# Lilypad_buffered.net
KiCad netlist of a schematic drawn in EAGLE
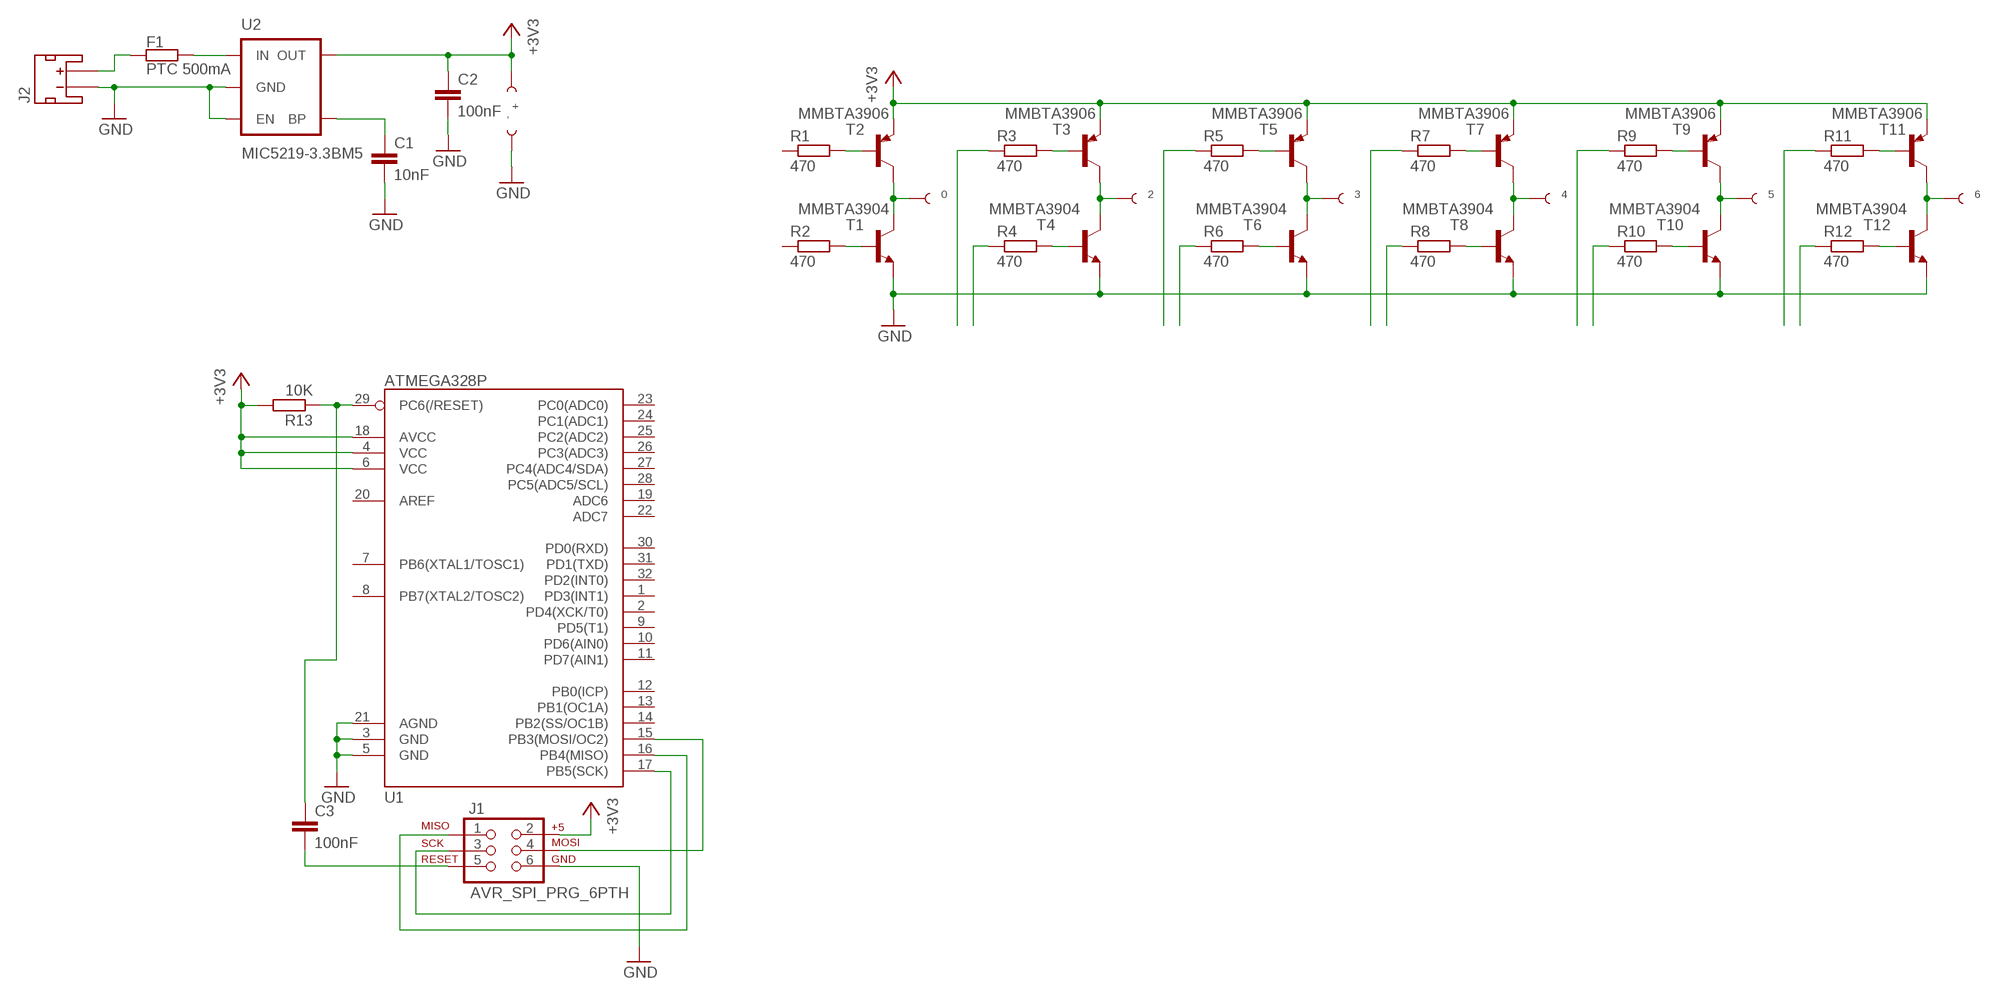
[diagram p0: schematic, sheet 1]

(export (version "E")
  (design (tool "Eeschema 10.0.6"))
  (components
    (comp (ref "C1")
      (value "10nF")
      (footprint "eagle-import:C0805K")
      (libsource (lib "eagle-import") (part "C-EUC0805K"))
    )
    (comp (ref "C2")
      (value "100nF")
      (footprint "eagle-import:C0805K")
      (libsource (lib "eagle-import") (part "C-EUC0805K"))
    )
    (comp (ref "C3")
      (value "100nF")
      (footprint "eagle-import:C0805K")
      (libsource (lib "eagle-import") (part "C-EUC0805K"))
    )
    (comp (ref "F1")
      (value "PTC 500mA")
      (footprint "eagle-import:SMD-2012")
      (libsource (lib "eagle-import") (part "RESISTENCIA-SMD-2012"))
    )
    (comp (ref "J1")
      (value "AVR_SPI_PRG_6PTH")
      (footprint "eagle-import:2X3")
      (libsource (lib "eagle-import") (part "AVR_SPI_PRG_6PTH"))
    )
    (comp (ref "J2")
      (value "JST_2MM_MALE")
      (footprint "eagle-import:JST-2-SMD")
      (libsource (lib "eagle-import") (part "JST_2MM_MALE"))
    )
    (comp (ref "R1")
      (value "470")
      (footprint "eagle-import:R0603")
      (libsource (lib "eagle-import") (part "R-EU_R0603"))
    )
    (comp (ref "R2")
      (value "470")
      (footprint "eagle-import:R0603")
      (libsource (lib "eagle-import") (part "R-EU_R0603"))
    )
    (comp (ref "R3")
      (value "470")
      (footprint "eagle-import:R0603")
      (libsource (lib "eagle-import") (part "R-EU_R0603"))
    )
    (comp (ref "R4")
      (value "470")
      (footprint "eagle-import:R0603")
      (libsource (lib "eagle-import") (part "R-EU_R0603"))
    )
    (comp (ref "R5")
      (value "470")
      (footprint "eagle-import:R0603")
      (libsource (lib "eagle-import") (part "R-EU_R0603"))
    )
    (comp (ref "R6")
      (value "470")
      (footprint "eagle-import:R0603")
      (libsource (lib "eagle-import") (part "R-EU_R0603"))
    )
    (comp (ref "R7")
      (value "470")
      (footprint "eagle-import:R0603")
      (libsource (lib "eagle-import") (part "R-EU_R0603"))
    )
    (comp (ref "R8")
      (value "470")
      (footprint "eagle-import:R0603")
      (libsource (lib "eagle-import") (part "R-EU_R0603"))
    )
    (comp (ref "R9")
      (value "470")
      (footprint "eagle-import:R0603")
      (libsource (lib "eagle-import") (part "R-EU_R0603"))
    )
    (comp (ref "R10")
      (value "470")
      (footprint "eagle-import:R0603")
      (libsource (lib "eagle-import") (part "R-EU_R0603"))
    )
    (comp (ref "R11")
      (value "470")
      (footprint "eagle-import:R0603")
      (libsource (lib "eagle-import") (part "R-EU_R0603"))
    )
    (comp (ref "R12")
      (value "470")
      (footprint "eagle-import:R0603")
      (libsource (lib "eagle-import") (part "R-EU_R0603"))
    )
    (comp (ref "R13")
      (value "10K")
      (footprint "eagle-import:R0603")
      (libsource (lib "eagle-import") (part "R-EU_R0603"))
    )
    (comp (ref "T1")
      (value "MMBTA3904")
      (footprint "eagle-import:SOT23-BEC")
      (libsource (lib "eagle-import") (part "-NPN-SOT23-BECMMBT3904LT1"))
    )
    (comp (ref "T2")
      (value "MMBTA3906")
      (footprint "eagle-import:SOT23-BEC")
      (libsource (lib "eagle-import") (part "-PNP-SOT23-BECMMBT3906LT1"))
    )
    (comp (ref "T3")
      (value "MMBTA3906")
      (footprint "eagle-import:SOT23-BEC")
      (libsource (lib "eagle-import") (part "-PNP-SOT23-BECMMBT3906LT1"))
    )
    (comp (ref "T4")
      (value "MMBTA3904")
      (footprint "eagle-import:SOT23-BEC")
      (libsource (lib "eagle-import") (part "-NPN-SOT23-BECMMBT3904LT1"))
    )
    (comp (ref "T5")
      (value "MMBTA3906")
      (footprint "eagle-import:SOT23-BEC")
      (libsource (lib "eagle-import") (part "-PNP-SOT23-BECMMBT3906LT1"))
    )
    (comp (ref "T6")
      (value "MMBTA3904")
      (footprint "eagle-import:SOT23-BEC")
      (libsource (lib "eagle-import") (part "-NPN-SOT23-BECMMBT3904LT1"))
    )
    (comp (ref "T7")
      (value "MMBTA3906")
      (footprint "eagle-import:SOT23-BEC")
      (libsource (lib "eagle-import") (part "-PNP-SOT23-BECMMBT3906LT1"))
    )
    (comp (ref "T8")
      (value "MMBTA3904")
      (footprint "eagle-import:SOT23-BEC")
      (libsource (lib "eagle-import") (part "-NPN-SOT23-BECMMBT3904LT1"))
    )
    (comp (ref "T9")
      (value "MMBTA3906")
      (footprint "eagle-import:SOT23-BEC")
      (libsource (lib "eagle-import") (part "-PNP-SOT23-BECMMBT3906LT1"))
    )
    (comp (ref "T10")
      (value "MMBTA3904")
      (footprint "eagle-import:SOT23-BEC")
      (libsource (lib "eagle-import") (part "-NPN-SOT23-BECMMBT3904LT1"))
    )
    (comp (ref "T11")
      (value "MMBTA3906")
      (footprint "eagle-import:SOT23-BEC")
      (libsource (lib "eagle-import") (part "-PNP-SOT23-BECMMBT3906LT1"))
    )
    (comp (ref "T12")
      (value "MMBTA3904")
      (footprint "eagle-import:SOT23-BEC")
      (libsource (lib "eagle-import") (part "-NPN-SOT23-BECMMBT3904LT1"))
    )
    (comp (ref "U$1")
      (value "0")
      (footprint "eagle-import:PETAL-LONG-1-2SIDE")
      (libsource (lib "eagle-import") (part "SEWTAP9"))
    )
    (comp (ref "U$2")
      (value "2")
      (footprint "eagle-import:PETAL-LONG-1-2SIDE")
      (libsource (lib "eagle-import") (part "SEWTAP9"))
    )
    (comp (ref "U$3")
      (value "3")
      (footprint "eagle-import:PETAL-LONG-1-2SIDE")
      (libsource (lib "eagle-import") (part "SEWTAP9"))
    )
    (comp (ref "U$4")
      (value "4")
      (footprint "eagle-import:PETAL-LONG-1-2SIDE")
      (libsource (lib "eagle-import") (part "SEWTAP9"))
    )
    (comp (ref "U$5")
      (value "5")
      (footprint "eagle-import:PETAL-LONG-1-2SIDE")
      (libsource (lib "eagle-import") (part "SEWTAP9"))
    )
    (comp (ref "U$6")
      (value "6")
      (footprint "eagle-import:PETAL-LONG-1-2SIDE")
      (libsource (lib "eagle-import") (part "SEWTAP9"))
    )
    (comp (ref "U$9")
      (value "+")
      (footprint "eagle-import:PETAL-LONG-1-2SIDE")
      (libsource (lib "eagle-import") (part "SEWTAP9"))
    )
    (comp (ref "U$10")
      (value "-")
      (footprint "eagle-import:PETAL-LONG-1-2SIDE")
      (libsource (lib "eagle-import") (part "SEWTAP9"))
    )
    (comp (ref "U1")
      (value "ATMEGA328P")
      (footprint "eagle-import:TQFP32-08")
      (libsource (lib "eagle-import") (part "ATMEGA328_SMT"))
    )
    (comp (ref "U2")
      (value "MIC5219-3.3BM5")
      (footprint "eagle-import:SOT23-5")
      (libsource (lib "eagle-import") (part "MIC52053.3V"))
    )
  )
  (nets
    (net (code "1") (name "+3V3") (class "Default")
      (node (ref "C2") (pin "1") (pinfunction "1_1") (pintype "passive"))
      (node (ref "J1") (pin "2") (pinfunction "2_2") (pintype "passive"))
      (node (ref "R13") (pin "2") (pinfunction "2_2") (pintype "passive"))
      (node (ref "T11") (pin "E") (pinfunction "E_E") (pintype "passive"))
      (node (ref "T2") (pin "E") (pinfunction "E_E") (pintype "passive"))
      (node (ref "T3") (pin "E") (pinfunction "E_E") (pintype "passive"))
      (node (ref "T5") (pin "E") (pinfunction "E_E") (pintype "passive"))
      (node (ref "T7") (pin "E") (pinfunction "E_E") (pintype "passive"))
      (node (ref "T9") (pin "E") (pinfunction "E_E") (pintype "passive"))
      (node (ref "U$9") (pin "1") (pinfunction "1_1") (pintype "bidirectional"))
      (node (ref "U1") (pin "18") (pinfunction "AVCC_18") (pintype "bidirectional"))
      (node (ref "U1") (pin "4") (pinfunction "VCC_4") (pintype "bidirectional"))
      (node (ref "U1") (pin "6") (pinfunction "VCC_6") (pintype "bidirectional"))
      (node (ref "U2") (pin "5") (pinfunction "OUT_5") (pintype "passive"))
    )
    (net (code "2") (name "GND") (class "Default")
      (node (ref "C1") (pin "2") (pinfunction "2_2") (pintype "passive"))
      (node (ref "C2") (pin "2") (pinfunction "2_2") (pintype "passive"))
      (node (ref "J1") (pin "6") (pinfunction "6_6") (pintype "passive"))
      (node (ref "J2") (pin "1") (pinfunction "-_1") (pintype "bidirectional"))
      (node (ref "T1") (pin "E") (pinfunction "E_E") (pintype "passive"))
      (node (ref "T10") (pin "E") (pinfunction "E_E") (pintype "passive"))
      (node (ref "T12") (pin "E") (pinfunction "E_E") (pintype "passive"))
      (node (ref "T4") (pin "E") (pinfunction "E_E") (pintype "passive"))
      (node (ref "T6") (pin "E") (pinfunction "E_E") (pintype "passive"))
      (node (ref "T8") (pin "E") (pinfunction "E_E") (pintype "passive"))
      (node (ref "U$10") (pin "1") (pinfunction "1_1") (pintype "bidirectional"))
      (node (ref "U1") (pin "21") (pinfunction "AGND_21") (pintype "bidirectional"))
      (node (ref "U1") (pin "3") (pinfunction "GND_3") (pintype "bidirectional"))
      (node (ref "U1") (pin "5") (pinfunction "GND_5") (pintype "bidirectional"))
      (node (ref "U2") (pin "2") (pinfunction "GND_2") (pintype "input"))
      (node (ref "U2") (pin "3") (pinfunction "EN_3") (pintype "input"))
    )
    (net (code "3") (name "Net-(C3-Pad2)") (class "Default")
      (node (ref "C3") (pin "2") (pinfunction "2_2") (pintype "passive"))
      (node (ref "J1") (pin "5") (pinfunction "5_5") (pintype "passive"))
    )
    (net (code "4") (name "Net-(J2-+)") (class "Default")
      (node (ref "F1") (pin "P$2") (pinfunction "P$2_P$2") (pintype "bidirectional"))
      (node (ref "J2") (pin "2") (pinfunction "+_2") (pintype "bidirectional"))
    )
    (net (code "5") (name "Net-(R1-Pad2)") (class "Default")
      (node (ref "R1") (pin "2") (pinfunction "2_2") (pintype "passive"))
      (node (ref "T2") (pin "B") (pinfunction "B_B") (pintype "passive"))
    )
    (net (code "6") (name "Net-(R2-Pad2)") (class "Default")
      (node (ref "R2") (pin "2") (pinfunction "2_2") (pintype "passive"))
      (node (ref "T1") (pin "B") (pinfunction "B_B") (pintype "passive"))
    )
    (net (code "7") (name "Net-(R3-Pad2)") (class "Default")
      (node (ref "R3") (pin "2") (pinfunction "2_2") (pintype "passive"))
      (node (ref "T3") (pin "B") (pinfunction "B_B") (pintype "passive"))
    )
    (net (code "8") (name "Net-(R4-Pad2)") (class "Default")
      (node (ref "R4") (pin "2") (pinfunction "2_2") (pintype "passive"))
      (node (ref "T4") (pin "B") (pinfunction "B_B") (pintype "passive"))
    )
    (net (code "9") (name "Net-(R5-Pad2)") (class "Default")
      (node (ref "R5") (pin "2") (pinfunction "2_2") (pintype "passive"))
      (node (ref "T5") (pin "B") (pinfunction "B_B") (pintype "passive"))
    )
    (net (code "10") (name "Net-(R6-Pad2)") (class "Default")
      (node (ref "R6") (pin "2") (pinfunction "2_2") (pintype "passive"))
      (node (ref "T6") (pin "B") (pinfunction "B_B") (pintype "passive"))
    )
    (net (code "11") (name "Net-(R7-Pad2)") (class "Default")
      (node (ref "R7") (pin "2") (pinfunction "2_2") (pintype "passive"))
      (node (ref "T7") (pin "B") (pinfunction "B_B") (pintype "passive"))
    )
    (net (code "12") (name "Net-(R8-Pad2)") (class "Default")
      (node (ref "R8") (pin "2") (pinfunction "2_2") (pintype "passive"))
      (node (ref "T8") (pin "B") (pinfunction "B_B") (pintype "passive"))
    )
    (net (code "13") (name "Net-(R9-Pad2)") (class "Default")
      (node (ref "R9") (pin "2") (pinfunction "2_2") (pintype "passive"))
      (node (ref "T9") (pin "B") (pinfunction "B_B") (pintype "passive"))
    )
    (net (code "14") (name "Net-(R10-Pad2)") (class "Default")
      (node (ref "R10") (pin "2") (pinfunction "2_2") (pintype "passive"))
      (node (ref "T10") (pin "B") (pinfunction "B_B") (pintype "passive"))
    )
    (net (code "15") (name "Net-(R11-Pad2)") (class "Default")
      (node (ref "R11") (pin "2") (pinfunction "2_2") (pintype "passive"))
      (node (ref "T11") (pin "B") (pinfunction "B_B") (pintype "passive"))
    )
    (net (code "16") (name "Net-(R12-Pad2)") (class "Default")
      (node (ref "R12") (pin "2") (pinfunction "2_2") (pintype "passive"))
      (node (ref "T12") (pin "B") (pinfunction "B_B") (pintype "passive"))
    )
    (net (code "17") (name "Net-(T1-PadC)") (class "Default")
      (node (ref "T1") (pin "C") (pinfunction "C_C") (pintype "passive"))
      (node (ref "T2") (pin "C") (pinfunction "C_C") (pintype "passive"))
      (node (ref "U$1") (pin "1") (pinfunction "1_1") (pintype "bidirectional"))
    )
    (net (code "18") (name "Net-(T3-PadC)") (class "Default")
      (node (ref "T3") (pin "C") (pinfunction "C_C") (pintype "passive"))
      (node (ref "T4") (pin "C") (pinfunction "C_C") (pintype "passive"))
      (node (ref "U$2") (pin "1") (pinfunction "1_1") (pintype "bidirectional"))
    )
    (net (code "19") (name "Net-(T5-PadC)") (class "Default")
      (node (ref "T5") (pin "C") (pinfunction "C_C") (pintype "passive"))
      (node (ref "T6") (pin "C") (pinfunction "C_C") (pintype "passive"))
      (node (ref "U$3") (pin "1") (pinfunction "1_1") (pintype "bidirectional"))
    )
    (net (code "20") (name "Net-(T7-PadC)") (class "Default")
      (node (ref "T7") (pin "C") (pinfunction "C_C") (pintype "passive"))
      (node (ref "T8") (pin "C") (pinfunction "C_C") (pintype "passive"))
      (node (ref "U$4") (pin "1") (pinfunction "1_1") (pintype "bidirectional"))
    )
    (net (code "21") (name "Net-(T10-PadC)") (class "Default")
      (node (ref "T10") (pin "C") (pinfunction "C_C") (pintype "passive"))
      (node (ref "T9") (pin "C") (pinfunction "C_C") (pintype "passive"))
      (node (ref "U$5") (pin "1") (pinfunction "1_1") (pintype "bidirectional"))
    )
    (net (code "22") (name "Net-(T11-PadC)") (class "Default")
      (node (ref "T11") (pin "C") (pinfunction "C_C") (pintype "passive"))
      (node (ref "T12") (pin "C") (pinfunction "C_C") (pintype "passive"))
      (node (ref "U$6") (pin "1") (pinfunction "1_1") (pintype "bidirectional"))
    )
    (net (code "23") (name "Net-(U1-PB3(MOSI{slash}OC2))") (class "Default")
      (node (ref "J1") (pin "4") (pinfunction "4_4") (pintype "passive"))
      (node (ref "U1") (pin "15") (pinfunction "PB3(MOSI/OC2)_15") (pintype "bidirectional"))
    )
    (net (code "24") (name "Net-(U1-PB4(MISO))") (class "Default")
      (node (ref "J1") (pin "1") (pinfunction "1_1") (pintype "passive"))
      (node (ref "U1") (pin "16") (pinfunction "PB4(MISO)_16") (pintype "bidirectional"))
    )
    (net (code "25") (name "Net-(U1-PB5(SCK))") (class "Default")
      (node (ref "J1") (pin "3") (pinfunction "3_3") (pintype "passive"))
      (node (ref "U1") (pin "17") (pinfunction "PB5(SCK)_17") (pintype "bidirectional"))
    )
    (net (code "26") (name "Net-(U1-PC6({slash}RESET))") (class "Default")
      (node (ref "C3") (pin "1") (pinfunction "1_1") (pintype "passive"))
      (node (ref "R13") (pin "1") (pinfunction "1_1") (pintype "passive"))
      (node (ref "U1") (pin "29") (pinfunction "PC6(/RESET)_29") (pintype "bidirectional"))
    )
    (net (code "27") (name "Net-(U2-BP)") (class "Default")
      (node (ref "C1") (pin "1") (pinfunction "1_1") (pintype "passive"))
      (node (ref "U2") (pin "4") (pinfunction "BP_4") (pintype "input"))
    )
    (net (code "28") (name "Net-(U2-IN)") (class "Default")
      (node (ref "F1") (pin "P$1") (pinfunction "P$1_P$1") (pintype "bidirectional"))
      (node (ref "U2") (pin "1") (pinfunction "IN_1") (pintype "input"))
    )
    (net (code "29") (name "unconnected-(J2-PAD1-PadNC1)") (class "Default")
      (node (ref "J2") (pin "NC1") (pinfunction "PAD1_NC1") (pintype "bidirectional"))
    )
    (net (code "30") (name "unconnected-(J2-PAD2-PadNC2)") (class "Default")
      (node (ref "J2") (pin "NC2") (pinfunction "PAD2_NC2") (pintype "bidirectional"))
    )
    (net (code "31") (name "unconnected-(R1-Pad1)") (class "Default")
      (node (ref "R1") (pin "1") (pinfunction "1_1") (pintype "passive"))
    )
    (net (code "32") (name "unconnected-(R2-Pad1)") (class "Default")
      (node (ref "R2") (pin "1") (pinfunction "1_1") (pintype "passive"))
    )
    (net (code "33") (name "unconnected-(R3-Pad1)") (class "Default")
      (node (ref "R3") (pin "1") (pinfunction "1_1") (pintype "passive"))
    )
    (net (code "34") (name "unconnected-(R4-Pad1)") (class "Default")
      (node (ref "R4") (pin "1") (pinfunction "1_1") (pintype "passive"))
    )
    (net (code "35") (name "unconnected-(R5-Pad1)") (class "Default")
      (node (ref "R5") (pin "1") (pinfunction "1_1") (pintype "passive"))
    )
    (net (code "36") (name "unconnected-(R6-Pad1)") (class "Default")
      (node (ref "R6") (pin "1") (pinfunction "1_1") (pintype "passive"))
    )
    (net (code "37") (name "unconnected-(R7-Pad1)") (class "Default")
      (node (ref "R7") (pin "1") (pinfunction "1_1") (pintype "passive"))
    )
    (net (code "38") (name "unconnected-(R8-Pad1)") (class "Default")
      (node (ref "R8") (pin "1") (pinfunction "1_1") (pintype "passive"))
    )
    (net (code "39") (name "unconnected-(R9-Pad1)") (class "Default")
      (node (ref "R9") (pin "1") (pinfunction "1_1") (pintype "passive"))
    )
    (net (code "40") (name "unconnected-(R10-Pad1)") (class "Default")
      (node (ref "R10") (pin "1") (pinfunction "1_1") (pintype "passive"))
    )
    (net (code "41") (name "unconnected-(R11-Pad1)") (class "Default")
      (node (ref "R11") (pin "1") (pinfunction "1_1") (pintype "passive"))
    )
    (net (code "42") (name "unconnected-(R12-Pad1)") (class "Default")
      (node (ref "R12") (pin "1") (pinfunction "1_1") (pintype "passive"))
    )
    (net (code "43") (name "unconnected-(U1-ADC6-Pad19)") (class "Default")
      (node (ref "U1") (pin "19") (pinfunction "ADC6_19") (pintype "bidirectional"))
    )
    (net (code "44") (name "unconnected-(U1-ADC7-Pad22)") (class "Default")
      (node (ref "U1") (pin "22") (pinfunction "ADC7_22") (pintype "bidirectional"))
    )
    (net (code "45") (name "unconnected-(U1-AREF-Pad20)") (class "Default")
      (node (ref "U1") (pin "20") (pinfunction "AREF_20") (pintype "bidirectional"))
    )
    (net (code "46") (name "unconnected-(U1-PB0(ICP)-Pad12)") (class "Default")
      (node (ref "U1") (pin "12") (pinfunction "PB0(ICP)_12") (pintype "bidirectional"))
    )
    (net (code "47") (name "unconnected-(U1-PB1(OC1A)-Pad13)") (class "Default")
      (node (ref "U1") (pin "13") (pinfunction "PB1(OC1A)_13") (pintype "bidirectional"))
    )
    (net (code "48") (name "unconnected-(U1-PB2(SS{slash}OC1B)-Pad14)") (class "Default")
      (node (ref "U1") (pin "14") (pinfunction "PB2(SS/OC1B)_14") (pintype "bidirectional"))
    )
    (net (code "49") (name "unconnected-(U1-PB6(XTAL1{slash}TOSC1)-Pad7)") (class "Default")
      (node (ref "U1") (pin "7") (pinfunction "PB6(XTAL1/TOSC1)_7") (pintype "bidirectional"))
    )
    (net (code "50") (name "unconnected-(U1-PB7(XTAL2{slash}TOSC2)-Pad8)") (class "Default")
      (node (ref "U1") (pin "8") (pinfunction "PB7(XTAL2/TOSC2)_8") (pintype "bidirectional"))
    )
    (net (code "51") (name "unconnected-(U1-PC0(ADC0)-Pad23)") (class "Default")
      (node (ref "U1") (pin "23") (pinfunction "PC0(ADC0)_23") (pintype "bidirectional"))
    )
    (net (code "52") (name "unconnected-(U1-PC1(ADC1)-Pad24)") (class "Default")
      (node (ref "U1") (pin "24") (pinfunction "PC1(ADC1)_24") (pintype "bidirectional"))
    )
    (net (code "53") (name "unconnected-(U1-PC2(ADC2)-Pad25)") (class "Default")
      (node (ref "U1") (pin "25") (pinfunction "PC2(ADC2)_25") (pintype "bidirectional"))
    )
    (net (code "54") (name "unconnected-(U1-PC3(ADC3)-Pad26)") (class "Default")
      (node (ref "U1") (pin "26") (pinfunction "PC3(ADC3)_26") (pintype "bidirectional"))
    )
    (net (code "55") (name "unconnected-(U1-PC4(ADC4{slash}SDA)-Pad27)") (class "Default")
      (node (ref "U1") (pin "27") (pinfunction "PC4(ADC4/SDA)_27") (pintype "bidirectional"))
    )
    (net (code "56") (name "unconnected-(U1-PC5(ADC5{slash}SCL)-Pad28)") (class "Default")
      (node (ref "U1") (pin "28") (pinfunction "PC5(ADC5/SCL)_28") (pintype "bidirectional"))
    )
    (net (code "57") (name "unconnected-(U1-PD0(RXD)-Pad30)") (class "Default")
      (node (ref "U1") (pin "30") (pinfunction "PD0(RXD)_30") (pintype "bidirectional"))
    )
    (net (code "58") (name "unconnected-(U1-PD1(TXD)-Pad31)") (class "Default")
      (node (ref "U1") (pin "31") (pinfunction "PD1(TXD)_31") (pintype "bidirectional"))
    )
    (net (code "59") (name "unconnected-(U1-PD2(INT0)-Pad32)") (class "Default")
      (node (ref "U1") (pin "32") (pinfunction "PD2(INT0)_32") (pintype "bidirectional"))
    )
    (net (code "60") (name "unconnected-(U1-PD3(INT1)-Pad1)") (class "Default")
      (node (ref "U1") (pin "1") (pinfunction "PD3(INT1)_1") (pintype "bidirectional"))
    )
    (net (code "61") (name "unconnected-(U1-PD4(XCK{slash}T0)-Pad2)") (class "Default")
      (node (ref "U1") (pin "2") (pinfunction "PD4(XCK/T0)_2") (pintype "bidirectional"))
    )
    (net (code "62") (name "unconnected-(U1-PD5(T1)-Pad9)") (class "Default")
      (node (ref "U1") (pin "9") (pinfunction "PD5(T1)_9") (pintype "bidirectional"))
    )
    (net (code "63") (name "unconnected-(U1-PD6(AIN0)-Pad10)") (class "Default")
      (node (ref "U1") (pin "10") (pinfunction "PD6(AIN0)_10") (pintype "bidirectional"))
    )
    (net (code "64") (name "unconnected-(U1-PD7(AIN1)-Pad11)") (class "Default")
      (node (ref "U1") (pin "11") (pinfunction "PD7(AIN1)_11") (pintype "bidirectional"))
    )
  )
)
